# NixieTracker.net
KiCad netlist of a schematic drawn in EAGLE
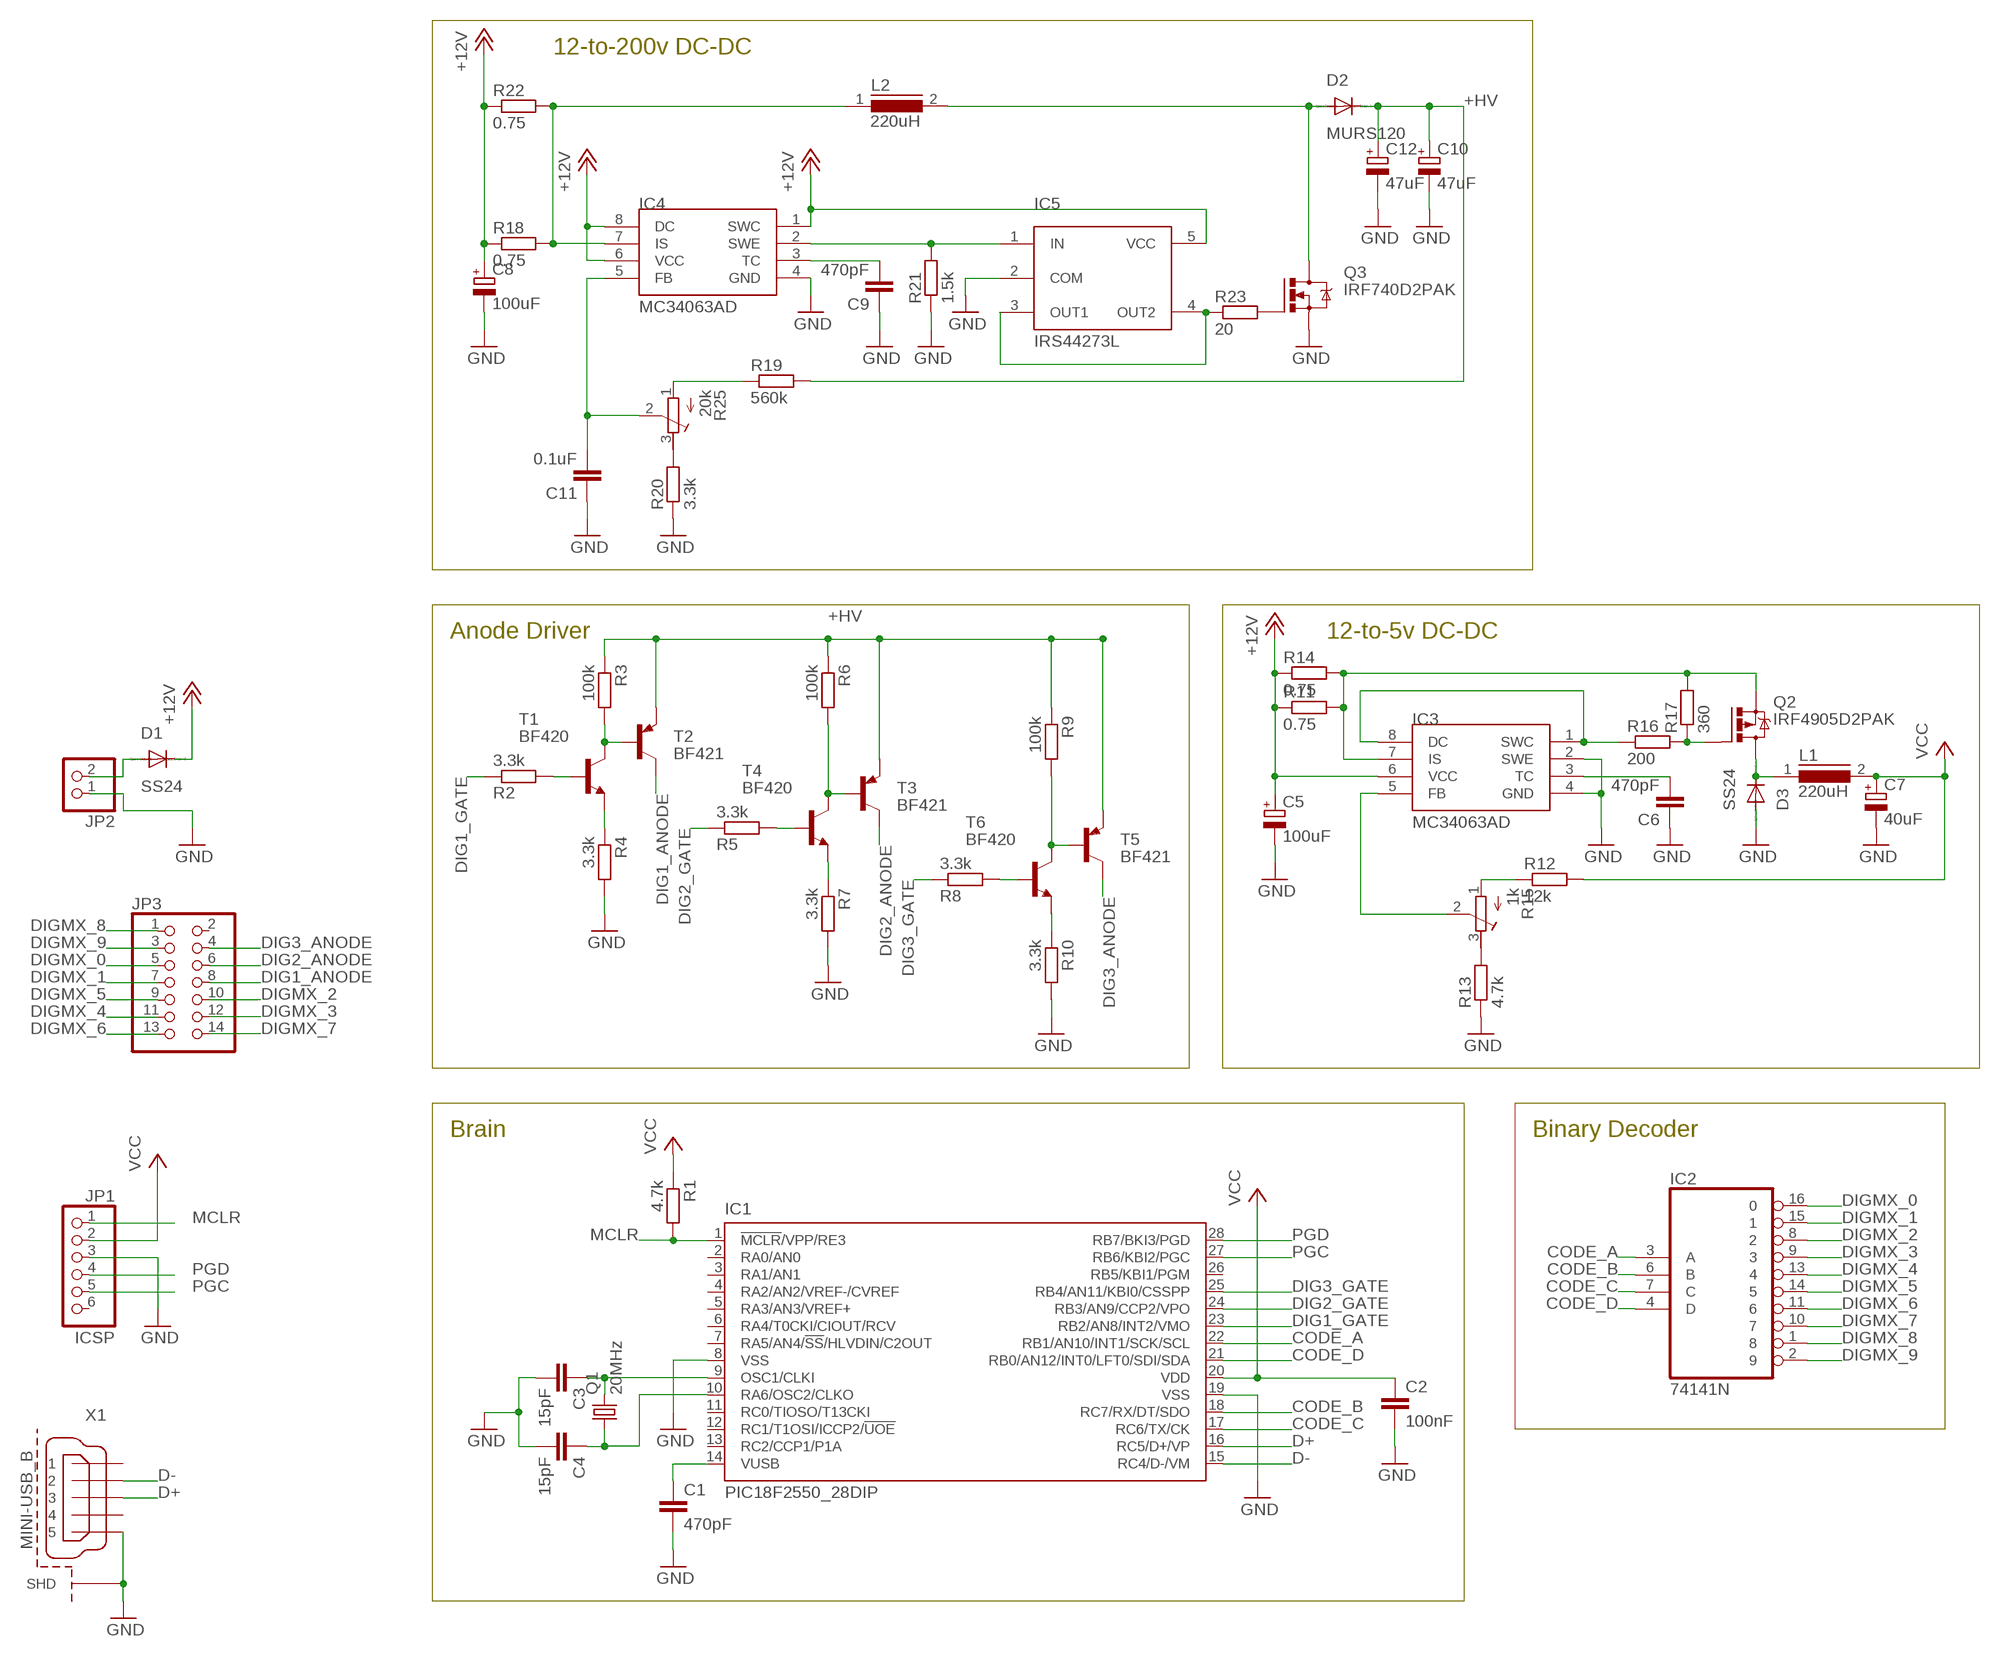
[diagram p0: schematic, sheet 1]

(export (version "E")
  (design (tool "Eeschema 10.0.6"))
  (components
    (comp (ref "C1")
      (value "470pF")
      (footprint "eagle-import:C050-024X044")
      (libsource (lib "eagle-import") (part "C-EU050-024X044"))
    )
    (comp (ref "C2")
      (value "100nF")
      (footprint "eagle-import:C050-024X044")
      (libsource (lib "eagle-import") (part "C-EU050-024X044"))
    )
    (comp (ref "C3")
      (value "15pF")
      (footprint "eagle-import:C050-024X044")
      (libsource (lib "eagle-import") (part "C-EU050-024X044"))
    )
    (comp (ref "C4")
      (value "15pF")
      (footprint "eagle-import:C050-024X044")
      (libsource (lib "eagle-import") (part "C-EU050-024X044"))
    )
    (comp (ref "C5")
      (value "100uF")
      (footprint "eagle-import:D_7343-31R")
      (libsource (lib "eagle-import") (part "CPOL-EUD/7343-31R"))
    )
    (comp (ref "C6")
      (value "470pF")
      (footprint "eagle-import:C1206K")
      (libsource (lib "eagle-import") (part "C-EUC1206K"))
    )
    (comp (ref "C7")
      (value "40uF")
      (footprint "eagle-import:C_6032-28R")
      (libsource (lib "eagle-import") (part "CPOL-EUC/6032-28R"))
    )
    (comp (ref "C8")
      (value "100uF")
      (footprint "eagle-import:D_7343-31R")
      (libsource (lib "eagle-import") (part "CPOL-EUD/7343-31R"))
    )
    (comp (ref "C9")
      (value "470pF")
      (footprint "eagle-import:C1206K")
      (libsource (lib "eagle-import") (part "C-EUC1206K"))
    )
    (comp (ref "C10")
      (value "47uF")
      (footprint "eagle-import:SANYO-OSCON_F13")
      (libsource (lib "eagle-import") (part "CPOL-EUSANYO_F13"))
    )
    (comp (ref "C11")
      (value "0.1uF")
      (footprint "eagle-import:C1206K")
      (libsource (lib "eagle-import") (part "C-EUC1206K"))
    )
    (comp (ref "C12")
      (value "47uF")
      (footprint "eagle-import:SANYO-OSCON_F13")
      (libsource (lib "eagle-import") (part "CPOL-EUSANYO_F13"))
    )
    (comp (ref "D1")
      (value "SS24")
      (footprint "eagle-import:DO214AA")
      (libsource (lib "eagle-import") (part "DIODE-DO214AA"))
    )
    (comp (ref "D2")
      (value "MURS120")
      (footprint "eagle-import:DO214AA")
      (libsource (lib "eagle-import") (part "DIODE-DO214AA"))
    )
    (comp (ref "D3")
      (value "SS24")
      (footprint "eagle-import:DO214AA")
      (libsource (lib "eagle-import") (part "DIODE-DO214AA"))
    )
    (comp (ref "IC1")
      (value "PIC18F2550_28DIP")
      (footprint "eagle-import:DIL28-3")
      (fields (field (name "MF") "MICROCHIP") (field (name "MPN") "PIC18F2550-I/SP"))
      (libsource (lib "eagle-import") (part "PIC18F2_28DIP550"))
    )
    (comp (ref "IC2")
      (value "74141N")
      (footprint "eagle-import:DIL16")
      (libsource (lib "eagle-import") (part "74141N"))
    )
    (comp (ref "IC3")
      (value "MC34063AD")
      (footprint "eagle-import:SOIC8")
      (libsource (lib "eagle-import") (part "MC34063AD"))
    )
    (comp (ref "IC4")
      (value "MC34063AD")
      (footprint "eagle-import:SOIC8")
      (libsource (lib "eagle-import") (part "MC34063AD"))
    )
    (comp (ref "IC5")
      (value "IRS44273L")
      (footprint "eagle-import:SOT23-5")
      (libsource (lib "eagle-import") (part "IRS44273L"))
    )
    (comp (ref "JP1")
      (value "ICSP")
      (footprint "eagle-import:1X06")
      (libsource (lib "eagle-import") (part "PINHD-1X6"))
    )
    (comp (ref "JP2")
      (value "PINHD-1X2")
      (footprint "eagle-import:1X02")
      (libsource (lib "eagle-import") (part "PINHD-1X2"))
    )
    (comp (ref "JP3")
      (value "PINHD-2X7")
      (footprint "eagle-import:2X07")
      (libsource (lib "eagle-import") (part "PINHD-2X7"))
    )
    (comp (ref "L1")
      (value "220uH")
      (footprint "eagle-import:DR125")
      (libsource (lib "eagle-import") (part "DR125"))
    )
    (comp (ref "L2")
      (value "220uH")
      (footprint "eagle-import:DR125")
      (libsource (lib "eagle-import") (part "DR125"))
    )
    (comp (ref "Q1")
      (value "20MHz")
      (footprint "eagle-import:HC49_S")
      (libsource (lib "eagle-import") (part "CRYSTALHC49S"))
    )
    (comp (ref "Q2")
      (value "IRF4905D2PAK")
      (footprint "eagle-import:D2PAK")
      (libsource (lib "eagle-import") (part "IRF4905D2PAK"))
    )
    (comp (ref "Q3")
      (value "IRF740D2PAK")
      (footprint "eagle-import:D2PAK")
      (libsource (lib "eagle-import") (part "IRF740D2PAK"))
    )
    (comp (ref "R1")
      (value "4.7k")
      (footprint "eagle-import:0207_2V")
      (libsource (lib "eagle-import") (part "R-EU_0207/2V"))
    )
    (comp (ref "R2")
      (value "3.3k")
      (footprint "eagle-import:0207_2V")
      (libsource (lib "eagle-import") (part "R-EU_0207/2V"))
    )
    (comp (ref "R3")
      (value "100k")
      (footprint "eagle-import:0207_5V")
      (libsource (lib "eagle-import") (part "R-EU_0207/5V"))
    )
    (comp (ref "R4")
      (value "3.3k")
      (footprint "eagle-import:0207_7")
      (libsource (lib "eagle-import") (part "R-EU_0207/7"))
    )
    (comp (ref "R5")
      (value "3.3k")
      (footprint "eagle-import:0207_2V")
      (libsource (lib "eagle-import") (part "R-EU_0207/2V"))
    )
    (comp (ref "R6")
      (value "100k")
      (footprint "eagle-import:0207_5V")
      (libsource (lib "eagle-import") (part "R-EU_0207/5V"))
    )
    (comp (ref "R7")
      (value "3.3k")
      (footprint "eagle-import:0207_7")
      (libsource (lib "eagle-import") (part "R-EU_0207/7"))
    )
    (comp (ref "R8")
      (value "3.3k")
      (footprint "eagle-import:0207_2V")
      (libsource (lib "eagle-import") (part "R-EU_0207/2V"))
    )
    (comp (ref "R9")
      (value "100k")
      (footprint "eagle-import:0207_5V")
      (libsource (lib "eagle-import") (part "R-EU_0207/5V"))
    )
    (comp (ref "R10")
      (value "3.3k")
      (footprint "eagle-import:0207_7")
      (libsource (lib "eagle-import") (part "R-EU_0207/7"))
    )
    (comp (ref "R11")
      (value "0.75")
      (footprint "eagle-import:R1206")
      (libsource (lib "eagle-import") (part "rcl-2_R-EU_R1206"))
    )
    (comp (ref "R12")
      (value "12k")
      (footprint "eagle-import:R1206")
      (libsource (lib "eagle-import") (part "rcl-2_R-EU_R1206"))
    )
    (comp (ref "R13")
      (value "4.7k")
      (footprint "eagle-import:R1206")
      (libsource (lib "eagle-import") (part "rcl-2_R-EU_R1206"))
    )
    (comp (ref "R14")
      (value "0.75")
      (footprint "eagle-import:R1206")
      (libsource (lib "eagle-import") (part "rcl-2_R-EU_R1206"))
    )
    (comp (ref "R15")
      (value "1k")
      (footprint "eagle-import:RTRIM4G_J")
      (libsource (lib "eagle-import") (part "R-TRIMM4G/J"))
    )
    (comp (ref "R16")
      (value "200")
      (footprint "eagle-import:R1206")
      (libsource (lib "eagle-import") (part "rcl-2_R-EU_R1206"))
    )
    (comp (ref "R17")
      (value "360")
      (footprint "eagle-import:R1206")
      (libsource (lib "eagle-import") (part "rcl-2_R-EU_R1206"))
    )
    (comp (ref "R18")
      (value "0.75")
      (footprint "eagle-import:R1206")
      (libsource (lib "eagle-import") (part "rcl-2_R-EU_R1206"))
    )
    (comp (ref "R19")
      (value "560k")
      (footprint "eagle-import:R1206")
      (libsource (lib "eagle-import") (part "rcl-2_R-EU_R1206"))
    )
    (comp (ref "R20")
      (value "3.3k")
      (footprint "eagle-import:R1206")
      (libsource (lib "eagle-import") (part "rcl-2_R-EU_R1206"))
    )
    (comp (ref "R21")
      (value "1.5k")
      (footprint "eagle-import:R1206")
      (libsource (lib "eagle-import") (part "rcl-2_R-EU_R1206"))
    )
    (comp (ref "R22")
      (value "0.75")
      (footprint "eagle-import:R1206")
      (libsource (lib "eagle-import") (part "rcl-2_R-EU_R1206"))
    )
    (comp (ref "R23")
      (value "20")
      (footprint "eagle-import:R1206")
      (libsource (lib "eagle-import") (part "rcl-2_R-EU_R1206"))
    )
    (comp (ref "R25")
      (value "20k")
      (footprint "eagle-import:RTRIM4G_J")
      (libsource (lib "eagle-import") (part "R-TRIMM4G/J"))
    )
    (comp (ref "T1")
      (value "BF420")
      (footprint "eagle-import:TO92-ECB")
      (libsource (lib "eagle-import") (part "-NPN-TO92-ECBBC368"))
    )
    (comp (ref "T2")
      (value "BF421")
      (footprint "eagle-import:TO92-ECB")
      (libsource (lib "eagle-import") (part "-PNP-TO92-ECB"))
    )
    (comp (ref "T3")
      (value "BF421")
      (footprint "eagle-import:TO92-ECB")
      (libsource (lib "eagle-import") (part "-PNP-TO92-ECB"))
    )
    (comp (ref "T4")
      (value "BF420")
      (footprint "eagle-import:TO92-ECB")
      (libsource (lib "eagle-import") (part "-NPN-TO92-ECBBC368"))
    )
    (comp (ref "T5")
      (value "BF421")
      (footprint "eagle-import:TO92-ECB")
      (libsource (lib "eagle-import") (part "-PNP-TO92-ECB"))
    )
    (comp (ref "T6")
      (value "BF420")
      (footprint "eagle-import:TO92-ECB")
      (libsource (lib "eagle-import") (part "-NPN-TO92-ECBBC368"))
    )
    (comp (ref "X1")
      (value "MINI-USB_B")
      (footprint "eagle-import:MINI-USB-B")
      (libsource (lib "eagle-import") (part "MINI-USB_B"))
    )
  )
  (nets
    (net (code "1") (name "+12V") (class "Default")
      (node (ref "C5") (pin "+") (pinfunction "+_+") (pintype "passive"))
      (node (ref "C8") (pin "+") (pinfunction "+_+") (pintype "passive"))
      (node (ref "D1") (pin "C") (pinfunction "C_C") (pintype "passive"))
      (node (ref "IC3") (pin "6") (pinfunction "VCC_6") (pintype "passive"))
      (node (ref "IC4") (pin "1") (pinfunction "SWC_1") (pintype "passive"))
      (node (ref "IC4") (pin "6") (pinfunction "VCC_6") (pintype "passive"))
      (node (ref "IC4") (pin "8") (pinfunction "DC_8") (pintype "passive"))
      (node (ref "IC5") (pin "5") (pinfunction "VCC_5") (pintype "power_in"))
      (node (ref "R11") (pin "1") (pinfunction "1_1") (pintype "passive"))
      (node (ref "R14") (pin "1") (pinfunction "1_1") (pintype "passive"))
      (node (ref "R18") (pin "1") (pinfunction "1_1") (pintype "passive"))
      (node (ref "R22") (pin "1") (pinfunction "1_1") (pintype "passive"))
    )
    (net (code "2") (name "/+HV") (class "Default")
      (node (ref "C10") (pin "+") (pinfunction "+_+") (pintype "passive"))
      (node (ref "C12") (pin "+") (pinfunction "+_+") (pintype "passive"))
      (node (ref "D2") (pin "C") (pinfunction "C_C") (pintype "passive"))
      (node (ref "R19") (pin "2") (pinfunction "2_2") (pintype "passive"))
      (node (ref "R3") (pin "1") (pinfunction "1_1") (pintype "passive"))
      (node (ref "R6") (pin "1") (pinfunction "1_1") (pintype "passive"))
      (node (ref "R9") (pin "1") (pinfunction "1_1") (pintype "passive"))
      (node (ref "T2") (pin "E") (pinfunction "E_E") (pintype "passive"))
      (node (ref "T3") (pin "E") (pinfunction "E_E") (pintype "passive"))
      (node (ref "T5") (pin "E") (pinfunction "E_E") (pintype "passive"))
    )
    (net (code "3") (name "/CODE_A") (class "Default")
      (node (ref "IC1") (pin "22") (pinfunction "RB1/AN10/INT1/SCK/SCL_22") (pintype "bidirectional"))
      (node (ref "IC2") (pin "3") (pinfunction "A_3") (pintype "input"))
    )
    (net (code "4") (name "/CODE_B") (class "Default")
      (node (ref "IC1") (pin "18") (pinfunction "RC7/RX/DT/SDO_18") (pintype "bidirectional"))
      (node (ref "IC2") (pin "6") (pinfunction "B_6") (pintype "input"))
    )
    (net (code "5") (name "/CODE_C") (class "Default")
      (node (ref "IC1") (pin "17") (pinfunction "RC6/TX/CK_17") (pintype "bidirectional"))
      (node (ref "IC2") (pin "7") (pinfunction "C_7") (pintype "input"))
    )
    (net (code "6") (name "/CODE_D") (class "Default")
      (node (ref "IC1") (pin "21") (pinfunction "RB0/AN12/INT0/LFT0/SDI/SDA_21") (pintype "bidirectional"))
      (node (ref "IC2") (pin "4") (pinfunction "D_4") (pintype "input"))
    )
    (net (code "7") (name "/D+") (class "Default")
      (node (ref "IC1") (pin "16") (pinfunction "RC5/D+/VP_16") (pintype "bidirectional"))
      (node (ref "X1") (pin "3") (pinfunction "3_3") (pintype "passive"))
    )
    (net (code "8") (name "/D-") (class "Default")
      (node (ref "IC1") (pin "15") (pinfunction "RC4/D-/VM_15") (pintype "bidirectional"))
      (node (ref "X1") (pin "2") (pinfunction "2_2") (pintype "passive"))
    )
    (net (code "9") (name "/DIG1_ANODE") (class "Default")
      (node (ref "JP3") (pin "8") (pinfunction "8_8") (pintype "passive"))
      (node (ref "T2") (pin "C") (pinfunction "C_C") (pintype "passive"))
    )
    (net (code "10") (name "/DIG1_GATE") (class "Default")
      (node (ref "IC1") (pin "23") (pinfunction "RB2/AN8/INT2/VMO_23") (pintype "bidirectional"))
      (node (ref "R2") (pin "1") (pinfunction "1_1") (pintype "passive"))
    )
    (net (code "11") (name "/DIG2_ANODE") (class "Default")
      (node (ref "JP3") (pin "6") (pinfunction "6_6") (pintype "passive"))
      (node (ref "T3") (pin "C") (pinfunction "C_C") (pintype "passive"))
    )
    (net (code "12") (name "/DIG2_GATE") (class "Default")
      (node (ref "IC1") (pin "24") (pinfunction "RB3/AN9/CCP2/VPO_24") (pintype "bidirectional"))
      (node (ref "R5") (pin "1") (pinfunction "1_1") (pintype "passive"))
    )
    (net (code "13") (name "/DIG3_ANODE") (class "Default")
      (node (ref "JP3") (pin "4") (pinfunction "4_4") (pintype "passive"))
      (node (ref "T5") (pin "C") (pinfunction "C_C") (pintype "passive"))
    )
    (net (code "14") (name "/DIG3_GATE") (class "Default")
      (node (ref "IC1") (pin "25") (pinfunction "RB4/AN11/KBI0/CSSPP_25") (pintype "bidirectional"))
      (node (ref "R8") (pin "1") (pinfunction "1_1") (pintype "passive"))
    )
    (net (code "15") (name "/DIGMX_0") (class "Default")
      (node (ref "IC2") (pin "16") (pinfunction "0_16") (pintype "open_collector"))
      (node (ref "JP3") (pin "5") (pinfunction "5_5") (pintype "passive"))
    )
    (net (code "16") (name "/DIGMX_1") (class "Default")
      (node (ref "IC2") (pin "15") (pinfunction "1_15") (pintype "open_collector"))
      (node (ref "JP3") (pin "7") (pinfunction "7_7") (pintype "passive"))
    )
    (net (code "17") (name "/DIGMX_2") (class "Default")
      (node (ref "IC2") (pin "8") (pinfunction "2_8") (pintype "open_collector"))
      (node (ref "JP3") (pin "10") (pinfunction "10_10") (pintype "passive"))
    )
    (net (code "18") (name "/DIGMX_3") (class "Default")
      (node (ref "IC2") (pin "9") (pinfunction "3_9") (pintype "open_collector"))
      (node (ref "JP3") (pin "12") (pinfunction "12_12") (pintype "passive"))
    )
    (net (code "19") (name "/DIGMX_4") (class "Default")
      (node (ref "IC2") (pin "13") (pinfunction "4_13") (pintype "open_collector"))
      (node (ref "JP3") (pin "11") (pinfunction "11_11") (pintype "passive"))
    )
    (net (code "20") (name "/DIGMX_5") (class "Default")
      (node (ref "IC2") (pin "14") (pinfunction "5_14") (pintype "open_collector"))
      (node (ref "JP3") (pin "9") (pinfunction "9_9") (pintype "passive"))
    )
    (net (code "21") (name "/DIGMX_6") (class "Default")
      (node (ref "IC2") (pin "11") (pinfunction "6_11") (pintype "open_collector"))
      (node (ref "JP3") (pin "13") (pinfunction "13_13") (pintype "passive"))
    )
    (net (code "22") (name "/DIGMX_7") (class "Default")
      (node (ref "IC2") (pin "10") (pinfunction "7_10") (pintype "open_collector"))
      (node (ref "JP3") (pin "14") (pinfunction "14_14") (pintype "passive"))
    )
    (net (code "23") (name "/DIGMX_8") (class "Default")
      (node (ref "IC2") (pin "1") (pinfunction "8_1") (pintype "open_collector"))
      (node (ref "JP3") (pin "1") (pinfunction "1_1") (pintype "passive"))
    )
    (net (code "24") (name "/DIGMX_9") (class "Default")
      (node (ref "IC2") (pin "2") (pinfunction "9_2") (pintype "open_collector"))
      (node (ref "JP3") (pin "3") (pinfunction "3_3") (pintype "passive"))
    )
    (net (code "25") (name "/MCLR") (class "Default")
      (node (ref "IC1") (pin "1") (pinfunction "~{MCLR}/VPP/RE3_1") (pintype "input"))
      (node (ref "JP1") (pin "1") (pinfunction "1_1") (pintype "passive"))
      (node (ref "R1") (pin "2") (pinfunction "2_2") (pintype "passive"))
    )
    (net (code "26") (name "/PGC") (class "Default")
      (node (ref "IC1") (pin "27") (pinfunction "RB6/KBI2/PGC_27") (pintype "bidirectional"))
      (node (ref "JP1") (pin "5") (pinfunction "5_5") (pintype "passive"))
    )
    (net (code "27") (name "/PGD") (class "Default")
      (node (ref "IC1") (pin "28") (pinfunction "RB7/BKI3/PGD_28") (pintype "bidirectional"))
      (node (ref "JP1") (pin "4") (pinfunction "4_4") (pintype "passive"))
    )
    (net (code "28") (name "GND") (class "Default")
      (node (ref "C1") (pin "2") (pinfunction "2_2") (pintype "passive"))
      (node (ref "C10") (pin "-") (pinfunction "-_-") (pintype "passive"))
      (node (ref "C11") (pin "1") (pinfunction "1_1") (pintype "passive"))
      (node (ref "C12") (pin "-") (pinfunction "-_-") (pintype "passive"))
      (node (ref "C2") (pin "2") (pinfunction "2_2") (pintype "passive"))
      (node (ref "C3") (pin "2") (pinfunction "2_2") (pintype "passive"))
      (node (ref "C4") (pin "2") (pinfunction "2_2") (pintype "passive"))
      (node (ref "C5") (pin "-") (pinfunction "-_-") (pintype "passive"))
      (node (ref "C6") (pin "1") (pinfunction "1_1") (pintype "passive"))
      (node (ref "C7") (pin "-") (pinfunction "-_-") (pintype "passive"))
      (node (ref "C8") (pin "-") (pinfunction "-_-") (pintype "passive"))
      (node (ref "C9") (pin "1") (pinfunction "1_1") (pintype "passive"))
      (node (ref "D3") (pin "A") (pinfunction "A_A") (pintype "passive"))
      (node (ref "IC1") (pin "19") (pinfunction "VSS_19") (pintype "power_in"))
      (node (ref "IC1") (pin "8") (pinfunction "VSS_8") (pintype "power_in"))
      (node (ref "IC3") (pin "2") (pinfunction "SWE_2") (pintype "passive"))
      (node (ref "IC3") (pin "4") (pinfunction "GND_4") (pintype "passive"))
      (node (ref "IC4") (pin "4") (pinfunction "GND_4") (pintype "passive"))
      (node (ref "IC5") (pin "2") (pinfunction "COM_2") (pintype "power_in"))
      (node (ref "JP1") (pin "3") (pinfunction "3_3") (pintype "passive"))
      (node (ref "JP2") (pin "1") (pinfunction "1_1") (pintype "passive"))
      (node (ref "Q3") (pin "3") (pinfunction "S_3") (pintype "passive"))
      (node (ref "R10") (pin "2") (pinfunction "2_2") (pintype "passive"))
      (node (ref "R13") (pin "1") (pinfunction "1_1") (pintype "passive"))
      (node (ref "R20") (pin "1") (pinfunction "1_1") (pintype "passive"))
      (node (ref "R21") (pin "1") (pinfunction "1_1") (pintype "passive"))
      (node (ref "R4") (pin "2") (pinfunction "2_2") (pintype "passive"))
      (node (ref "R7") (pin "2") (pinfunction "2_2") (pintype "passive"))
      (node (ref "X1") (pin "5") (pinfunction "5_5") (pintype "passive"))
      (node (ref "X1") (pin "M1") (pinfunction "SHD_M1") (pintype "passive"))
      (node (ref "X1") (pin "M2") (pinfunction "SHD_M2") (pintype "passive"))
      (node (ref "X1") (pin "M3") (pinfunction "SHD_M3") (pintype "passive"))
      (node (ref "X1") (pin "M4") (pinfunction "SHD_M4") (pintype "passive"))
    )
    (net (code "29") (name "Net-(D1-PadA)") (class "Default")
      (node (ref "D1") (pin "A") (pinfunction "A_A") (pintype "passive"))
      (node (ref "JP2") (pin "2") (pinfunction "2_2") (pintype "passive"))
    )
    (net (code "30") (name "Net-(IC1-OSC1{slash}CLKI)") (class "Default")
      (node (ref "C3") (pin "1") (pinfunction "1_1") (pintype "passive"))
      (node (ref "IC1") (pin "9") (pinfunction "OSC1/CLKI_9") (pintype "input"))
      (node (ref "Q1") (pin "2") (pinfunction "2_2") (pintype "passive"))
    )
    (net (code "31") (name "Net-(IC1-RA6{slash}OSC2{slash}CLKO)") (class "Default")
      (node (ref "C4") (pin "1") (pinfunction "1_1") (pintype "passive"))
      (node (ref "IC1") (pin "10") (pinfunction "RA6/OSC2/CLKO_10") (pintype "output"))
      (node (ref "Q1") (pin "1") (pinfunction "1_1") (pintype "passive"))
    )
    (net (code "32") (name "Net-(IC1-VUSB)") (class "Default")
      (node (ref "C1") (pin "1") (pinfunction "1_1") (pintype "passive"))
      (node (ref "IC1") (pin "14") (pinfunction "VUSB_14") (pintype "bidirectional"))
    )
    (net (code "33") (name "Net-(IC3-DC)") (class "Default")
      (node (ref "IC3") (pin "1") (pinfunction "SWC_1") (pintype "passive"))
      (node (ref "IC3") (pin "8") (pinfunction "DC_8") (pintype "passive"))
      (node (ref "R16") (pin "1") (pinfunction "1_1") (pintype "passive"))
    )
    (net (code "34") (name "Net-(IC3-FB)") (class "Default")
      (node (ref "IC3") (pin "5") (pinfunction "FB_5") (pintype "passive"))
      (node (ref "R15") (pin "2") (pinfunction "S_2") (pintype "passive"))
    )
    (net (code "35") (name "Net-(IC3-IS)") (class "Default")
      (node (ref "IC3") (pin "7") (pinfunction "IS_7") (pintype "passive"))
      (node (ref "Q2") (pin "3") (pinfunction "S_3") (pintype "passive"))
      (node (ref "R11") (pin "2") (pinfunction "2_2") (pintype "passive"))
      (node (ref "R14") (pin "2") (pinfunction "2_2") (pintype "passive"))
      (node (ref "R17") (pin "2") (pinfunction "2_2") (pintype "passive"))
    )
    (net (code "36") (name "Net-(IC3-TC)") (class "Default")
      (node (ref "C6") (pin "2") (pinfunction "2_2") (pintype "passive"))
      (node (ref "IC3") (pin "3") (pinfunction "TC_3") (pintype "passive"))
    )
    (net (code "37") (name "Net-(IC4-FB)") (class "Default")
      (node (ref "C11") (pin "2") (pinfunction "2_2") (pintype "passive"))
      (node (ref "IC4") (pin "5") (pinfunction "FB_5") (pintype "passive"))
      (node (ref "R25") (pin "2") (pinfunction "S_2") (pintype "passive"))
    )
    (net (code "38") (name "Net-(IC4-IS)") (class "Default")
      (node (ref "IC4") (pin "7") (pinfunction "IS_7") (pintype "passive"))
      (node (ref "L2") (pin "1") (pinfunction "1_1") (pintype "passive"))
      (node (ref "R18") (pin "2") (pinfunction "2_2") (pintype "passive"))
      (node (ref "R22") (pin "2") (pinfunction "2_2") (pintype "passive"))
    )
    (net (code "39") (name "Net-(IC4-SWE)") (class "Default")
      (node (ref "IC4") (pin "2") (pinfunction "SWE_2") (pintype "passive"))
      (node (ref "IC5") (pin "1") (pinfunction "IN_1") (pintype "input"))
      (node (ref "R21") (pin "2") (pinfunction "2_2") (pintype "passive"))
    )
    (net (code "40") (name "Net-(IC4-TC)") (class "Default")
      (node (ref "C9") (pin "2") (pinfunction "2_2") (pintype "passive"))
      (node (ref "IC4") (pin "3") (pinfunction "TC_3") (pintype "passive"))
    )
    (net (code "41") (name "Net-(IC5-OUT1)") (class "Default")
      (node (ref "IC5") (pin "3") (pinfunction "OUT1_3") (pintype "output"))
      (node (ref "IC5") (pin "4") (pinfunction "OUT2_4") (pintype "output"))
      (node (ref "R23") (pin "1") (pinfunction "1_1") (pintype "passive"))
    )
    (net (code "42") (name "Net-(Q2-D)") (class "Default")
      (node (ref "D3") (pin "C") (pinfunction "C_C") (pintype "passive"))
      (node (ref "L1") (pin "1") (pinfunction "1_1") (pintype "passive"))
      (node (ref "Q2") (pin "4") (pinfunction "D_4") (pintype "passive"))
    )
    (net (code "43") (name "Net-(Q2-G)") (class "Default")
      (node (ref "Q2") (pin "1") (pinfunction "G_1") (pintype "passive"))
      (node (ref "R16") (pin "2") (pinfunction "2_2") (pintype "passive"))
      (node (ref "R17") (pin "1") (pinfunction "1_1") (pintype "passive"))
    )
    (net (code "44") (name "Net-(Q3-D)") (class "Default")
      (node (ref "D2") (pin "A") (pinfunction "A_A") (pintype "passive"))
      (node (ref "L2") (pin "2") (pinfunction "2_2") (pintype "passive"))
      (node (ref "Q3") (pin "4") (pinfunction "D_4") (pintype "passive"))
    )
    (net (code "45") (name "Net-(Q3-G)") (class "Default")
      (node (ref "Q3") (pin "1") (pinfunction "G_1") (pintype "passive"))
      (node (ref "R23") (pin "2") (pinfunction "2_2") (pintype "passive"))
    )
    (net (code "46") (name "Net-(R2-Pad2)") (class "Default")
      (node (ref "R2") (pin "2") (pinfunction "2_2") (pintype "passive"))
      (node (ref "T1") (pin "B") (pinfunction "B_B") (pintype "passive"))
    )
    (net (code "47") (name "Net-(R3-Pad2)") (class "Default")
      (node (ref "R3") (pin "2") (pinfunction "2_2") (pintype "passive"))
      (node (ref "T1") (pin "C") (pinfunction "C_C") (pintype "passive"))
      (node (ref "T2") (pin "B") (pinfunction "B_B") (pintype "passive"))
    )
    (net (code "48") (name "Net-(R4-Pad1)") (class "Default")
      (node (ref "R4") (pin "1") (pinfunction "1_1") (pintype "passive"))
      (node (ref "T1") (pin "E") (pinfunction "E_E") (pintype "passive"))
    )
    (net (code "49") (name "Net-(R5-Pad2)") (class "Default")
      (node (ref "R5") (pin "2") (pinfunction "2_2") (pintype "passive"))
      (node (ref "T4") (pin "B") (pinfunction "B_B") (pintype "passive"))
    )
    (net (code "50") (name "Net-(R6-Pad2)") (class "Default")
      (node (ref "R6") (pin "2") (pinfunction "2_2") (pintype "passive"))
      (node (ref "T3") (pin "B") (pinfunction "B_B") (pintype "passive"))
      (node (ref "T4") (pin "C") (pinfunction "C_C") (pintype "passive"))
    )
    (net (code "51") (name "Net-(R7-Pad1)") (class "Default")
      (node (ref "R7") (pin "1") (pinfunction "1_1") (pintype "passive"))
      (node (ref "T4") (pin "E") (pinfunction "E_E") (pintype "passive"))
    )
    (net (code "52") (name "Net-(R8-Pad2)") (class "Default")
      (node (ref "R8") (pin "2") (pinfunction "2_2") (pintype "passive"))
      (node (ref "T6") (pin "B") (pinfunction "B_B") (pintype "passive"))
    )
    (net (code "53") (name "Net-(R9-Pad2)") (class "Default")
      (node (ref "R9") (pin "2") (pinfunction "2_2") (pintype "passive"))
      (node (ref "T5") (pin "B") (pinfunction "B_B") (pintype "passive"))
      (node (ref "T6") (pin "C") (pinfunction "C_C") (pintype "passive"))
    )
    (net (code "54") (name "Net-(R10-Pad1)") (class "Default")
      (node (ref "R10") (pin "1") (pinfunction "1_1") (pintype "passive"))
      (node (ref "T6") (pin "E") (pinfunction "E_E") (pintype "passive"))
    )
    (net (code "55") (name "Net-(R15-A)") (class "Default")
      (node (ref "R12") (pin "1") (pinfunction "1_1") (pintype "passive"))
      (node (ref "R15") (pin "1") (pinfunction "A_1") (pintype "passive"))
    )
    (net (code "56") (name "Net-(R15-E)") (class "Default")
      (node (ref "R13") (pin "2") (pinfunction "2_2") (pintype "passive"))
      (node (ref "R15") (pin "3") (pinfunction "E_3") (pintype "passive"))
    )
    (net (code "57") (name "Net-(R25-A)") (class "Default")
      (node (ref "R19") (pin "1") (pinfunction "1_1") (pintype "passive"))
      (node (ref "R25") (pin "1") (pinfunction "A_1") (pintype "passive"))
    )
    (net (code "58") (name "Net-(R25-E)") (class "Default")
      (node (ref "R20") (pin "2") (pinfunction "2_2") (pintype "passive"))
      (node (ref "R25") (pin "3") (pinfunction "E_3") (pintype "passive"))
    )
    (net (code "59") (name "VCC") (class "Default")
      (node (ref "C2") (pin "1") (pinfunction "1_1") (pintype "passive"))
      (node (ref "C7") (pin "+") (pinfunction "+_+") (pintype "passive"))
      (node (ref "IC1") (pin "20") (pinfunction "VDD_20") (pintype "power_in"))
      (node (ref "JP1") (pin "2") (pinfunction "2_2") (pintype "passive"))
      (node (ref "L1") (pin "2") (pinfunction "2_2") (pintype "passive"))
      (node (ref "R1") (pin "1") (pinfunction "1_1") (pintype "passive"))
      (node (ref "R12") (pin "2") (pinfunction "2_2") (pintype "passive"))
    )
    (net (code "60") (name "unconnected-(IC1-RA0{slash}AN0-Pad2)") (class "Default")
      (node (ref "IC1") (pin "2") (pinfunction "RA0/AN0_2") (pintype "bidirectional"))
    )
    (net (code "61") (name "unconnected-(IC1-RA1{slash}AN1-Pad3)") (class "Default")
      (node (ref "IC1") (pin "3") (pinfunction "RA1/AN1_3") (pintype "bidirectional"))
    )
    (net (code "62") (name "unconnected-(IC1-RA2{slash}AN2{slash}VREF-{slash}CVREF-Pad4)") (class "Default")
      (node (ref "IC1") (pin "4") (pinfunction "RA2/AN2/VREF-/CVREF_4") (pintype "bidirectional"))
    )
    (net (code "63") (name "unconnected-(IC1-RA3{slash}AN3{slash}VREF+-Pad5)") (class "Default")
      (node (ref "IC1") (pin "5") (pinfunction "RA3/AN3/VREF+_5") (pintype "bidirectional"))
    )
    (net (code "64") (name "unconnected-(IC1-RA4{slash}T0CKI{slash}CIOUT{slash}RCV-Pad6)") (class "Default")
      (node (ref "IC1") (pin "6") (pinfunction "RA4/T0CKI/CIOUT/RCV_6") (pintype "bidirectional"))
    )
    (net (code "65") (name "unconnected-(IC1-RA5{slash}AN4{slash}~{SS}{slash}HLVDIN{slash}C2OUT-Pad7)") (class "Default")
      (node (ref "IC1") (pin "7") (pinfunction "RA5/AN4/~{SS}/HLVDIN/C2OUT_7") (pintype "bidirectional"))
    )
    (net (code "66") (name "unconnected-(IC1-RB5{slash}KBI1{slash}PGM-Pad26)") (class "Default")
      (node (ref "IC1") (pin "26") (pinfunction "RB5/KBI1/PGM_26") (pintype "bidirectional"))
    )
    (net (code "67") (name "unconnected-(IC1-RC0{slash}TIOSO{slash}T13CKI-Pad11)") (class "Default")
      (node (ref "IC1") (pin "11") (pinfunction "RC0/TIOSO/T13CKI_11") (pintype "bidirectional"))
    )
    (net (code "68") (name "unconnected-(IC1-RC1{slash}T1OSI{slash}ICCP2{slash}~{UOE}-Pad12)") (class "Default")
      (node (ref "IC1") (pin "12") (pinfunction "RC1/T1OSI/ICCP2/~{UOE}_12") (pintype "bidirectional"))
    )
    (net (code "69") (name "unconnected-(IC1-RC2{slash}CCP1{slash}P1A-Pad13)") (class "Default")
      (node (ref "IC1") (pin "13") (pinfunction "RC2/CCP1/P1A_13") (pintype "bidirectional"))
    )
    (net (code "70") (name "unconnected-(JP1-Pad6)") (class "Default")
      (node (ref "JP1") (pin "6") (pinfunction "6_6") (pintype "passive"))
    )
    (net (code "71") (name "unconnected-(JP3-Pad2)") (class "Default")
      (node (ref "JP3") (pin "2") (pinfunction "2_2") (pintype "passive"))
    )
    (net (code "72") (name "unconnected-(X1-Pad1)") (class "Default")
      (node (ref "X1") (pin "1") (pinfunction "1_1") (pintype "passive"))
    )
    (net (code "73") (name "unconnected-(X1-Pad4)") (class "Default")
      (node (ref "X1") (pin "4") (pinfunction "4_4") (pintype "passive"))
    )
  )
)
